# Summation_synth_and_line.net
KiCad netlist of a schematic drawn in EAGLE
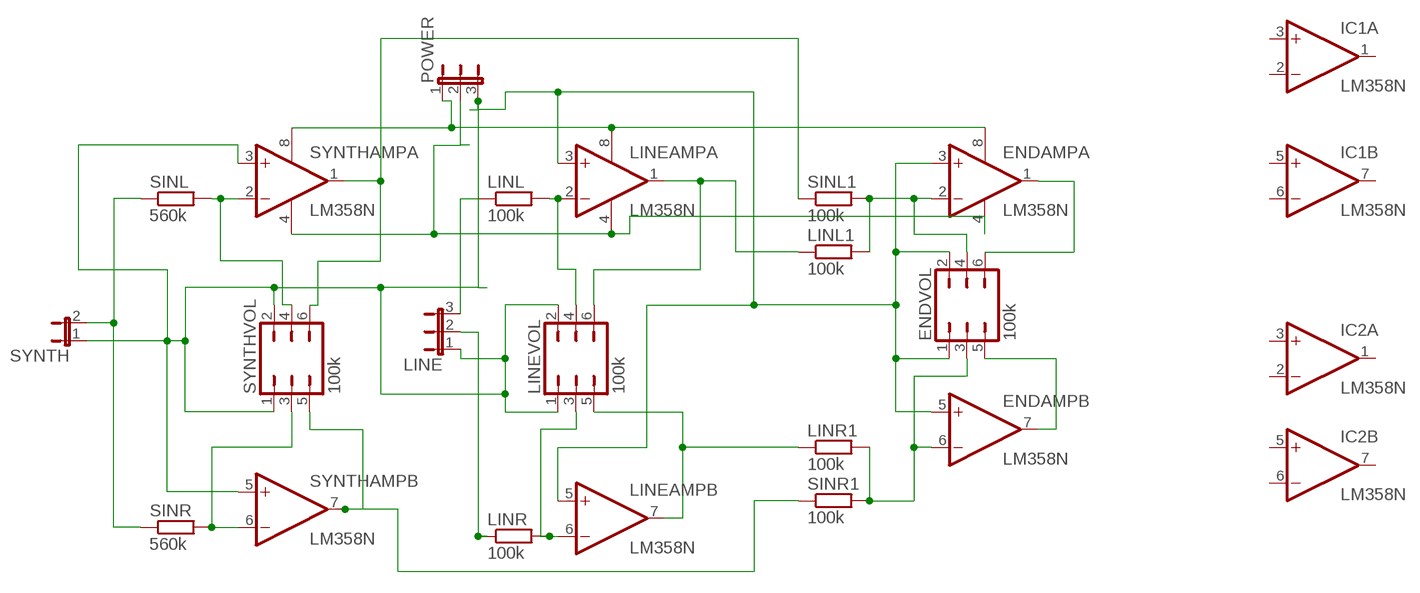
[diagram p0: schematic, sheet 1]

(export (version "E")
  (design (tool "Eeschema 10.0.6"))
  (components
    (comp (ref "ENDAMP")
      (value "LM358N")
      (footprint "eagle-import:DIL08")
      (libsource (lib "eagle-import") (part "LM358N"))
    )
    (comp (ref "ENDVOL")
      (value "100k")
      (footprint "eagle-import:JP3Q")
      (libsource (lib "eagle-import") (part "JP3Q"))
    )
    (comp (ref "IC1")
      (value "LM358N")
      (footprint "eagle-import:DIL08")
      (libsource (lib "eagle-import") (part "LM358N"))
    )
    (comp (ref "IC2")
      (value "LM358N")
      (footprint "eagle-import:DIL08")
      (libsource (lib "eagle-import") (part "LM358N"))
    )
    (comp (ref "LINE")
      (value "JP2E")
      (footprint "eagle-import:JP2")
      (libsource (lib "eagle-import") (part "JP2E"))
    )
    (comp (ref "LINEAMP")
      (value "LM358N")
      (footprint "eagle-import:DIL08")
      (libsource (lib "eagle-import") (part "LM358N"))
    )
    (comp (ref "LINEVOL")
      (value "100k")
      (footprint "eagle-import:JP3Q")
      (libsource (lib "eagle-import") (part "JP3Q"))
    )
    (comp (ref "LINL")
      (value "100k")
      (footprint "eagle-import:0207_7")
      (libsource (lib "eagle-import") (part "R-EU_0207/7"))
    )
    (comp (ref "LINL1")
      (value "100k")
      (footprint "eagle-import:0207_7")
      (libsource (lib "eagle-import") (part "R-EU_0207/7"))
    )
    (comp (ref "LINR")
      (value "100k")
      (footprint "eagle-import:0207_7")
      (libsource (lib "eagle-import") (part "R-EU_0207/7"))
    )
    (comp (ref "LINR1")
      (value "100k")
      (footprint "eagle-import:0207_7")
      (libsource (lib "eagle-import") (part "R-EU_0207/7"))
    )
    (comp (ref "POWER")
      (value "JP2E")
      (footprint "eagle-import:JP2")
      (libsource (lib "eagle-import") (part "JP2E"))
    )
    (comp (ref "SINL")
      (value "560k")
      (footprint "eagle-import:0207_7")
      (libsource (lib "eagle-import") (part "R-EU_0207/7"))
    )
    (comp (ref "SINL1")
      (value "100k")
      (footprint "eagle-import:0207_7")
      (libsource (lib "eagle-import") (part "R-EU_0207/7"))
    )
    (comp (ref "SINR")
      (value "560k")
      (footprint "eagle-import:0207_7")
      (libsource (lib "eagle-import") (part "R-EU_0207/7"))
    )
    (comp (ref "SINR1")
      (value "100k")
      (footprint "eagle-import:0207_7")
      (libsource (lib "eagle-import") (part "R-EU_0207/7"))
    )
    (comp (ref "SYNTH")
      (value "JP1E")
      (footprint "eagle-import:JP1")
      (libsource (lib "eagle-import") (part "JP1E"))
    )
    (comp (ref "SYNTHAMP")
      (value "LM358N")
      (footprint "eagle-import:DIL08")
      (libsource (lib "eagle-import") (part "LM358N"))
    )
    (comp (ref "SYNTHVOL")
      (value "100k")
      (footprint "eagle-import:JP3Q")
      (libsource (lib "eagle-import") (part "JP3Q"))
    )
  )
  (nets
    (net (code "1") (name "Net-(ENDAMPA-+IN)") (class "Default")
      (node (ref "ENDAMP") (pin "3") (pinfunction "+IN_3") (pintype "input"))
      (node (ref "ENDAMP") (pin "5") (pinfunction "+IN_5") (pintype "input"))
      (node (ref "ENDVOL") (pin "1") (pinfunction "1_1") (pintype "passive"))
      (node (ref "ENDVOL") (pin "2") (pinfunction "2_2") (pintype "passive"))
      (node (ref "LINE") (pin "1") (pinfunction "1_1") (pintype "passive"))
      (node (ref "LINEAMP") (pin "3") (pinfunction "+IN_3") (pintype "input"))
      (node (ref "LINEAMP") (pin "5") (pinfunction "+IN_5") (pintype "input"))
      (node (ref "LINEVOL") (pin "1") (pinfunction "1_1") (pintype "passive"))
      (node (ref "LINEVOL") (pin "2") (pinfunction "2_2") (pintype "passive"))
      (node (ref "POWER") (pin "3") (pinfunction "3_3") (pintype "passive"))
      (node (ref "SYNTH") (pin "1") (pinfunction "1_1") (pintype "passive"))
      (node (ref "SYNTHAMP") (pin "3") (pinfunction "+IN_3") (pintype "input"))
      (node (ref "SYNTHAMP") (pin "5") (pinfunction "+IN_5") (pintype "input"))
      (node (ref "SYNTHVOL") (pin "1") (pinfunction "1_1") (pintype "passive"))
      (node (ref "SYNTHVOL") (pin "2") (pinfunction "2_2") (pintype "passive"))
    )
    (net (code "2") (name "Net-(ENDAMPA--IN)") (class "Default")
      (node (ref "ENDAMP") (pin "2") (pinfunction "-IN_2") (pintype "input"))
      (node (ref "ENDVOL") (pin "4") (pinfunction "4_4") (pintype "passive"))
      (node (ref "LINL1") (pin "2") (pinfunction "2_2") (pintype "passive"))
      (node (ref "SINL1") (pin "2") (pinfunction "2_2") (pintype "passive"))
    )
    (net (code "3") (name "Net-(ENDAMPA-OUT)") (class "Default")
      (node (ref "ENDAMP") (pin "1") (pinfunction "OUT_1") (pintype "output"))
      (node (ref "ENDVOL") (pin "6") (pinfunction "6_6") (pintype "passive"))
    )
    (net (code "4") (name "Net-(ENDAMPB--IN)") (class "Default")
      (node (ref "ENDAMP") (pin "6") (pinfunction "-IN_6") (pintype "input"))
      (node (ref "ENDVOL") (pin "3") (pinfunction "3_3") (pintype "passive"))
      (node (ref "LINR1") (pin "2") (pinfunction "2_2") (pintype "passive"))
      (node (ref "SINR1") (pin "2") (pinfunction "2_2") (pintype "passive"))
    )
    (net (code "5") (name "Net-(ENDAMPB-OUT)") (class "Default")
      (node (ref "ENDAMP") (pin "7") (pinfunction "OUT_7") (pintype "output"))
      (node (ref "ENDVOL") (pin "5") (pinfunction "5_5") (pintype "passive"))
    )
    (net (code "6") (name "Net-(ENDAMPC-V+)") (class "Default")
      (node (ref "ENDAMP") (pin "8") (pinfunction "V+_8") (pintype "power_in"))
      (node (ref "LINEAMP") (pin "8") (pinfunction "V+_8") (pintype "power_in"))
      (node (ref "POWER") (pin "1") (pinfunction "1_1") (pintype "passive"))
      (node (ref "SYNTHAMP") (pin "8") (pinfunction "V+_8") (pintype "power_in"))
    )
    (net (code "7") (name "Net-(ENDAMPC-V-)") (class "Default")
      (node (ref "ENDAMP") (pin "4") (pinfunction "V-_4") (pintype "power_in"))
      (node (ref "LINEAMP") (pin "4") (pinfunction "V-_4") (pintype "power_in"))
      (node (ref "POWER") (pin "2") (pinfunction "2_2") (pintype "passive"))
      (node (ref "SYNTHAMP") (pin "4") (pinfunction "V-_4") (pintype "power_in"))
    )
    (net (code "8") (name "Net-(LINE-Pad2)") (class "Default")
      (node (ref "LINE") (pin "2") (pinfunction "2_2") (pintype "passive"))
      (node (ref "LINR") (pin "1") (pinfunction "1_1") (pintype "passive"))
    )
    (net (code "9") (name "Net-(LINE-Pad3)") (class "Default")
      (node (ref "LINE") (pin "3") (pinfunction "3_3") (pintype "passive"))
      (node (ref "LINL") (pin "1") (pinfunction "1_1") (pintype "passive"))
    )
    (net (code "10") (name "Net-(LINEAMPA--IN)") (class "Default")
      (node (ref "LINEAMP") (pin "2") (pinfunction "-IN_2") (pintype "input"))
      (node (ref "LINEVOL") (pin "4") (pinfunction "4_4") (pintype "passive"))
      (node (ref "LINL") (pin "2") (pinfunction "2_2") (pintype "passive"))
    )
    (net (code "11") (name "Net-(LINEAMPA-OUT)") (class "Default")
      (node (ref "LINEAMP") (pin "1") (pinfunction "OUT_1") (pintype "output"))
      (node (ref "LINEVOL") (pin "6") (pinfunction "6_6") (pintype "passive"))
      (node (ref "LINL1") (pin "1") (pinfunction "1_1") (pintype "passive"))
    )
    (net (code "12") (name "Net-(LINEAMPB--IN)") (class "Default")
      (node (ref "LINEAMP") (pin "6") (pinfunction "-IN_6") (pintype "input"))
      (node (ref "LINEVOL") (pin "3") (pinfunction "3_3") (pintype "passive"))
      (node (ref "LINR") (pin "2") (pinfunction "2_2") (pintype "passive"))
    )
    (net (code "13") (name "Net-(LINEAMPB-OUT)") (class "Default")
      (node (ref "LINEAMP") (pin "7") (pinfunction "OUT_7") (pintype "output"))
      (node (ref "LINEVOL") (pin "5") (pinfunction "5_5") (pintype "passive"))
      (node (ref "LINR1") (pin "1") (pinfunction "1_1") (pintype "passive"))
    )
    (net (code "14") (name "Net-(SINL-Pad1)") (class "Default")
      (node (ref "SINL") (pin "1") (pinfunction "1_1") (pintype "passive"))
      (node (ref "SINR") (pin "1") (pinfunction "1_1") (pintype "passive"))
      (node (ref "SYNTH") (pin "2") (pinfunction "2_2") (pintype "passive"))
    )
    (net (code "15") (name "Net-(SYNTHAMPA--IN)") (class "Default")
      (node (ref "SINL") (pin "2") (pinfunction "2_2") (pintype "passive"))
      (node (ref "SYNTHAMP") (pin "2") (pinfunction "-IN_2") (pintype "input"))
      (node (ref "SYNTHVOL") (pin "4") (pinfunction "4_4") (pintype "passive"))
    )
    (net (code "16") (name "Net-(SYNTHAMPA-OUT)") (class "Default")
      (node (ref "SINL1") (pin "1") (pinfunction "1_1") (pintype "passive"))
      (node (ref "SYNTHAMP") (pin "1") (pinfunction "OUT_1") (pintype "output"))
      (node (ref "SYNTHVOL") (pin "6") (pinfunction "6_6") (pintype "passive"))
    )
    (net (code "17") (name "Net-(SYNTHAMPB--IN)") (class "Default")
      (node (ref "SINR") (pin "2") (pinfunction "2_2") (pintype "passive"))
      (node (ref "SYNTHAMP") (pin "6") (pinfunction "-IN_6") (pintype "input"))
      (node (ref "SYNTHVOL") (pin "3") (pinfunction "3_3") (pintype "passive"))
    )
    (net (code "18") (name "Net-(SYNTHAMPB-OUT)") (class "Default")
      (node (ref "SINR1") (pin "1") (pinfunction "1_1") (pintype "passive"))
      (node (ref "SYNTHAMP") (pin "7") (pinfunction "OUT_7") (pintype "output"))
      (node (ref "SYNTHVOL") (pin "5") (pinfunction "5_5") (pintype "passive"))
    )
    (net (code "19") (name "unconnected-(IC1A-+IN-Pad3)") (class "Default")
      (node (ref "IC1") (pin "3") (pinfunction "+IN_3") (pintype "input"))
    )
    (net (code "20") (name "unconnected-(IC1A--IN-Pad2)") (class "Default")
      (node (ref "IC1") (pin "2") (pinfunction "-IN_2") (pintype "input"))
    )
    (net (code "21") (name "unconnected-(IC1A-OUT-Pad1)") (class "Default")
      (node (ref "IC1") (pin "1") (pinfunction "OUT_1") (pintype "output"))
    )
    (net (code "22") (name "unconnected-(IC1B-+IN-Pad5)") (class "Default")
      (node (ref "IC1") (pin "5") (pinfunction "+IN_5") (pintype "input"))
    )
    (net (code "23") (name "unconnected-(IC1B--IN-Pad6)") (class "Default")
      (node (ref "IC1") (pin "6") (pinfunction "-IN_6") (pintype "input"))
    )
    (net (code "24") (name "unconnected-(IC1B-OUT-Pad7)") (class "Default")
      (node (ref "IC1") (pin "7") (pinfunction "OUT_7") (pintype "output"))
    )
    (net (code "25") (name "unconnected-(IC2A-+IN-Pad3)") (class "Default")
      (node (ref "IC2") (pin "3") (pinfunction "+IN_3") (pintype "input"))
    )
    (net (code "26") (name "unconnected-(IC2A--IN-Pad2)") (class "Default")
      (node (ref "IC2") (pin "2") (pinfunction "-IN_2") (pintype "input"))
    )
    (net (code "27") (name "unconnected-(IC2A-OUT-Pad1)") (class "Default")
      (node (ref "IC2") (pin "1") (pinfunction "OUT_1") (pintype "output"))
    )
    (net (code "28") (name "unconnected-(IC2B-+IN-Pad5)") (class "Default")
      (node (ref "IC2") (pin "5") (pinfunction "+IN_5") (pintype "input"))
    )
    (net (code "29") (name "unconnected-(IC2B--IN-Pad6)") (class "Default")
      (node (ref "IC2") (pin "6") (pinfunction "-IN_6") (pintype "input"))
    )
    (net (code "30") (name "unconnected-(IC2B-OUT-Pad7)") (class "Default")
      (node (ref "IC2") (pin "7") (pinfunction "OUT_7") (pintype "output"))
    )
  )
)
